# PicoClockV1.net
KiCad netlist of a schematic drawn in Altium Designer
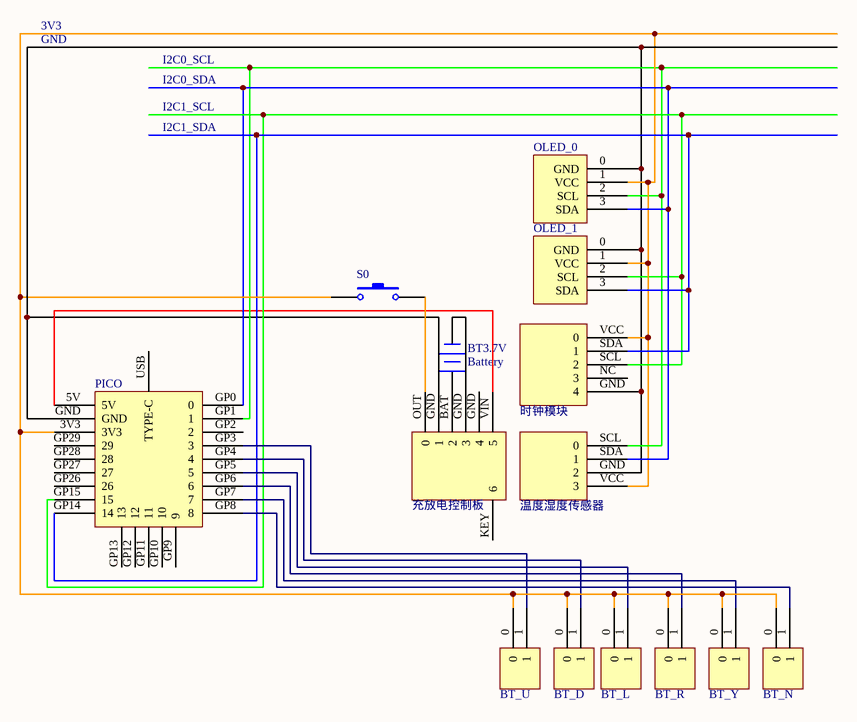
[diagram p0: PicoClockV1.SchDoc]

(export (version "E")
  (design (tool "Eeschema 10.0.6"))
  (components
    (comp (ref "BT3.7V")
      (value "Battery")
      (footprint "BAT-2")
      (description "Multicell Battery")
      (fields (field (name "PUBLISHER") "Altium Limited"))
      (libsource (lib "Miscellaneous Devices") (part "Battery"))
    )
    (comp (ref "BT_D") (value "*") (libsource (lib "*") (part "button")))
    (comp (ref "BT_L") (value "*") (libsource (lib "*") (part "button")))
    (comp (ref "BT_N") (value "*") (libsource (lib "*") (part "button")))
    (comp (ref "BT_R") (value "*") (libsource (lib "*") (part "button")))
    (comp (ref "BT_U") (value "*") (libsource (lib "*") (part "button")))
    (comp (ref "BT_Y") (value "*") (libsource (lib "*") (part "button")))
    (comp (ref "OLED_0") (value "*") (libsource (lib "*") (part "OLED_0")))
    (comp (ref "OLED_1") (value "*") (libsource (lib "*") (part "OLED_0")))
    (comp (ref "PICO") (value "*") (libsource (lib "*") (part "minipico")))
    (comp (ref "S0")
      (value "SW-PB")
      (footprint "SPST-2")
      (description "Switch")
      (fields (field (name "PUBLISHER") "Altium Limited"))
      (libsource (lib "Miscellaneous Devices") (part "SW-PB"))
    )
    (comp (ref "充放电控制板") (value "*") (libsource (lib "*") (part "batterycontroller")))
    (comp (ref "时钟模块") (value "*") (libsource (lib "*") (part "ds3231")))
    (comp (ref "温度湿度传感器") (value "*") (libsource (lib "*") (part "sht30")))
  )
  (nets
    (net (code "1") (name "Net-(BT3.7V--)") (class "Default")
      (node (ref "BT3.7V") (pin "2") (pinfunction "-_2") (pintype "passive"))
      (node (ref "充放电控制板") (pin "GND") (pinfunction "3_GND") (pintype "passive"))
    )
    (net (code "2") (name "Net-(OLED_0-GND)") (class "Default")
      (node (ref "OLED_0") (pin "0") (pinfunction "GND_0") (pintype "passive"))
      (node (ref "OLED_1") (pin "0") (pinfunction "GND_0") (pintype "passive"))
      (node (ref "PICO") (pin "GND") (pinfunction "GND_GND") (pintype "passive"))
      (node (ref "充放电控制板") (pin "GND") (pinfunction "1_GND") (pintype "passive"))
      (node (ref "时钟模块") (pin "GND") (pinfunction "4_GND") (pintype "passive"))
      (node (ref "温度湿度传感器") (pin "GND") (pinfunction "2_GND") (pintype "passive"))
    )
    (net (code "3") (name "Net-(OLED_0-SCL)") (class "Default")
      (node (ref "OLED_0") (pin "2") (pinfunction "SCL_2") (pintype "passive"))
      (node (ref "PICO") (pin "GP1") (pinfunction "1_GP1") (pintype "passive"))
      (node (ref "温度湿度传感器") (pin "SCL") (pinfunction "0_SCL") (pintype "passive"))
    )
    (net (code "4") (name "Net-(OLED_0-SDA)") (class "Default")
      (node (ref "OLED_0") (pin "3") (pinfunction "SDA_3") (pintype "passive"))
      (node (ref "PICO") (pin "GP0") (pinfunction "0_GP0") (pintype "passive"))
      (node (ref "温度湿度传感器") (pin "SDA") (pinfunction "1_SDA") (pintype "passive"))
    )
    (net (code "5") (name "Net-(OLED_0-VCC)") (class "Default")
      (node (ref "BT_D") (pin "0") (pinfunction "0_0") (pintype "passive"))
      (node (ref "BT_L") (pin "0") (pinfunction "0_0") (pintype "passive"))
      (node (ref "BT_N") (pin "0") (pinfunction "0_0") (pintype "passive"))
      (node (ref "BT_R") (pin "0") (pinfunction "0_0") (pintype "passive"))
      (node (ref "BT_U") (pin "0") (pinfunction "0_0") (pintype "passive"))
      (node (ref "BT_Y") (pin "0") (pinfunction "0_0") (pintype "passive"))
      (node (ref "OLED_0") (pin "1") (pinfunction "VCC_1") (pintype "passive"))
      (node (ref "OLED_1") (pin "1") (pinfunction "VCC_1") (pintype "passive"))
      (node (ref "PICO") (pin "3V3") (pinfunction "3V3_3V3") (pintype "passive"))
      (node (ref "S0") (pin "1") (pinfunction "1_1") (pintype "passive"))
      (node (ref "时钟模块") (pin "VCC") (pinfunction "0_VCC") (pintype "passive"))
      (node (ref "温度湿度传感器") (pin "VCC") (pinfunction "3_VCC") (pintype "passive"))
    )
    (net (code "6") (name "Net-(OLED_1-SCL)") (class "Default")
      (node (ref "OLED_1") (pin "2") (pinfunction "SCL_2") (pintype "passive"))
      (node (ref "PICO") (pin "GP15") (pinfunction "15_GP15") (pintype "passive"))
      (node (ref "时钟模块") (pin "SCL") (pinfunction "2_SCL") (pintype "passive"))
    )
    (net (code "7") (name "Net-(OLED_1-SDA)") (class "Default")
      (node (ref "OLED_1") (pin "3") (pinfunction "SDA_3") (pintype "passive"))
      (node (ref "PICO") (pin "GP14") (pinfunction "14_GP14") (pintype "passive"))
      (node (ref "时钟模块") (pin "SDA") (pinfunction "1_SDA") (pintype "passive"))
    )
    (net (code "8") (name "Net-(PICO-3)") (class "Default")
      (node (ref "BT_U") (pin "1") (pinfunction "1_1") (pintype "passive"))
      (node (ref "PICO") (pin "GP3") (pinfunction "3_GP3") (pintype "passive"))
    )
    (net (code "9") (name "Net-(PICO-4)") (class "Default")
      (node (ref "BT_D") (pin "1") (pinfunction "1_1") (pintype "passive"))
      (node (ref "PICO") (pin "GP4") (pinfunction "4_GP4") (pintype "passive"))
    )
    (net (code "10") (name "Net-(PICO-5)") (class "Default")
      (node (ref "BT_L") (pin "1") (pinfunction "1_1") (pintype "passive"))
      (node (ref "PICO") (pin "GP5") (pinfunction "5_GP5") (pintype "passive"))
    )
    (net (code "11") (name "Net-(PICO-6)") (class "Default")
      (node (ref "BT_R") (pin "1") (pinfunction "1_1") (pintype "passive"))
      (node (ref "PICO") (pin "GP6") (pinfunction "6_GP6") (pintype "passive"))
    )
    (net (code "12") (name "Net-(PICO-7)") (class "Default")
      (node (ref "BT_Y") (pin "1") (pinfunction "1_1") (pintype "passive"))
      (node (ref "PICO") (pin "GP7") (pinfunction "7_GP7") (pintype "passive"))
    )
    (net (code "13") (name "Net-(PICO-8)") (class "Default")
      (node (ref "BT_N") (pin "1") (pinfunction "1_1") (pintype "passive"))
      (node (ref "PICO") (pin "GP8") (pinfunction "8_GP8") (pintype "passive"))
    )
    (net (code "14") (name "Net-(充放电控制板-0)") (class "Default")
      (node (ref "S0") (pin "2") (pinfunction "2_2") (pintype "passive"))
      (node (ref "充放电控制板") (pin "OUT") (pinfunction "0_OUT") (pintype "passive"))
    )
    (net (code "15") (name "Net-(充放电控制板-5)") (class "Default")
      (node (ref "PICO") (pin "5V") (pinfunction "5V_5V") (pintype "passive"))
      (node (ref "充放电控制板") (pin "VIN") (pinfunction "5_VIN") (pintype "passive"))
    )
    (net (code "16") (name "unconnected-(BT3.7V-+-Pad1)") (class "Default")
      (node (ref "BT3.7V") (pin "1") (pinfunction "+_1") (pintype "passive"))
    )
    (net (code "17") (name "unconnected-(PICO-2-PadGP2)") (class "Default")
      (node (ref "PICO") (pin "GP2") (pinfunction "2_GP2") (pintype "passive"))
    )
    (net (code "18") (name "unconnected-(PICO-9-PadGP9)") (class "Default")
      (node (ref "PICO") (pin "GP9") (pinfunction "9_GP9") (pintype "passive"))
    )
    (net (code "19") (name "unconnected-(PICO-10-PadGP10)") (class "Default")
      (node (ref "PICO") (pin "GP10") (pinfunction "10_GP10") (pintype "passive"))
    )
    (net (code "20") (name "unconnected-(PICO-11-PadGP11)") (class "Default")
      (node (ref "PICO") (pin "GP11") (pinfunction "11_GP11") (pintype "passive"))
    )
    (net (code "21") (name "unconnected-(PICO-12-PadGP12)") (class "Default")
      (node (ref "PICO") (pin "GP12") (pinfunction "12_GP12") (pintype "passive"))
    )
    (net (code "22") (name "unconnected-(PICO-13-PadGP13)") (class "Default")
      (node (ref "PICO") (pin "GP13") (pinfunction "13_GP13") (pintype "passive"))
    )
    (net (code "23") (name "unconnected-(PICO-26-PadGP26)") (class "Default")
      (node (ref "PICO") (pin "GP26") (pinfunction "26_GP26") (pintype "passive"))
    )
    (net (code "24") (name "unconnected-(PICO-27-PadGP27)") (class "Default")
      (node (ref "PICO") (pin "GP27") (pinfunction "27_GP27") (pintype "passive"))
    )
    (net (code "25") (name "unconnected-(PICO-28-PadGP28)") (class "Default")
      (node (ref "PICO") (pin "GP28") (pinfunction "28_GP28") (pintype "passive"))
    )
    (net (code "26") (name "unconnected-(PICO-29-PadGP29)") (class "Default")
      (node (ref "PICO") (pin "GP29") (pinfunction "29_GP29") (pintype "passive"))
    )
    (net (code "27") (name "unconnected-(PICO-TYPE-C-PadUSB)") (class "Default")
      (node (ref "PICO") (pin "USB") (pinfunction "TYPE-C_USB") (pintype "passive"))
    )
    (net (code "28") (name "unconnected-(充放电控制板-2-PadBAT)") (class "Default")
      (node (ref "充放电控制板") (pin "BAT") (pinfunction "2_BAT") (pintype "passive"))
    )
    (net (code "29") (name "unconnected-(充放电控制板-4-PadGND)") (class "Default")
      (node (ref "充放电控制板") (pin "GND") (pinfunction "4_GND") (pintype "passive"))
    )
    (net (code "30") (name "unconnected-(充放电控制板-6-PadKEY)") (class "Default")
      (node (ref "充放电控制板") (pin "KEY") (pinfunction "6_KEY") (pintype "passive"))
    )
    (net (code "31") (name "unconnected-(时钟模块-3-PadNC)") (class "Default")
      (node (ref "时钟模块") (pin "NC") (pinfunction "3_NC") (pintype "passive"))
    )
  )
)
